# POS3V3.net
KiCad netlist of a schematic drawn in Altium Designer
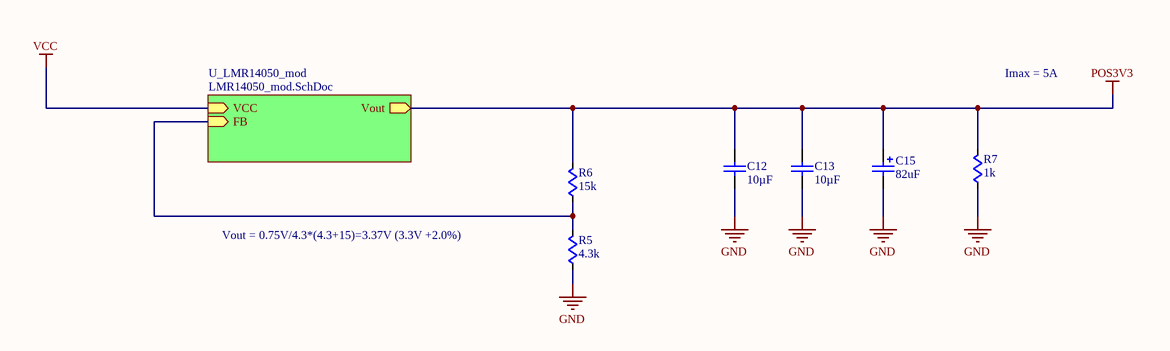
[diagram p0: POS3V3.SchDoc]

(export (version "E")
  (design (tool "Eeschema 10.0.6"))
  (components
    (comp (ref "C12")
      (value "10µF")
      (footprint "C0805")
      (description "capacitor")
      (fields (field (name "Comment") "Cap"))
      (libsource (lib "ChipComponents") (part "Cap"))
    )
    (comp (ref "C13")
      (value "10µF")
      (footprint "C0805")
      (description "capacitor")
      (fields (field (name "Comment") "Cap"))
      (libsource (lib "ChipComponents") (part "Cap"))
    )
    (comp (ref "C15")
      (value "82uF")
      (footprint "CAP_EEFK_D8")
      (description "Polarized Capacitor (Surface Mount)")
      (fields (field (name "MANUFACTURER_PART_NUMBER") "EEEFK1V680XP"))
      (libsource (lib "AEVC-lib") (part "EEEFK1V680XP"))
    )
    (comp (ref "R5")
      (value "4.3k")
      (footprint "R0805")
      (description "resistor")
      (fields (field (name "Comment") "Res"))
      (libsource (lib "ChipComponents") (part "Res"))
    )
    (comp (ref "R6")
      (value "15k")
      (footprint "R0805")
      (description "resistor")
      (fields (field (name "Comment") "Res"))
      (libsource (lib "ChipComponents") (part "Res"))
    )
    (comp (ref "R7")
      (value "1k")
      (footprint "R0805")
      (description "resistor")
      (fields (field (name "Comment") "Res"))
      (libsource (lib "ChipComponents") (part "Res"))
    )
  )
  (nets
    (net (code "1") (name "/FB") (class "Default")
      (node (ref "R5") (pin "2") (pinfunction "2_2") (pintype "passive"))
      (node (ref "R6") (pin "1") (pinfunction "1_1") (pintype "passive"))
    )
    (net (code "2") (name "GND") (class "Default")
      (node (ref "C12") (pin "1") (pinfunction "1_1") (pintype "passive"))
      (node (ref "C13") (pin "1") (pinfunction "1_1") (pintype "passive"))
      (node (ref "C15") (pin "2") (pinfunction "2_2") (pintype "passive"))
      (node (ref "R5") (pin "1") (pinfunction "1_1") (pintype "passive"))
      (node (ref "R7") (pin "1") (pinfunction "1_1") (pintype "passive"))
    )
    (net (code "3") (name "POS3V3") (class "Default")
      (node (ref "C12") (pin "2") (pinfunction "2_2") (pintype "passive"))
      (node (ref "C13") (pin "2") (pinfunction "2_2") (pintype "passive"))
      (node (ref "C15") (pin "1") (pinfunction "1_1") (pintype "passive"))
      (node (ref "R6") (pin "2") (pinfunction "2_2") (pintype "passive"))
      (node (ref "R7") (pin "2") (pinfunction "2_2") (pintype "passive"))
    )
  )
)
